# 39-996_-_SM_Clock-Timer.net
KiCad netlist of a schematic drawn in Altium Designer
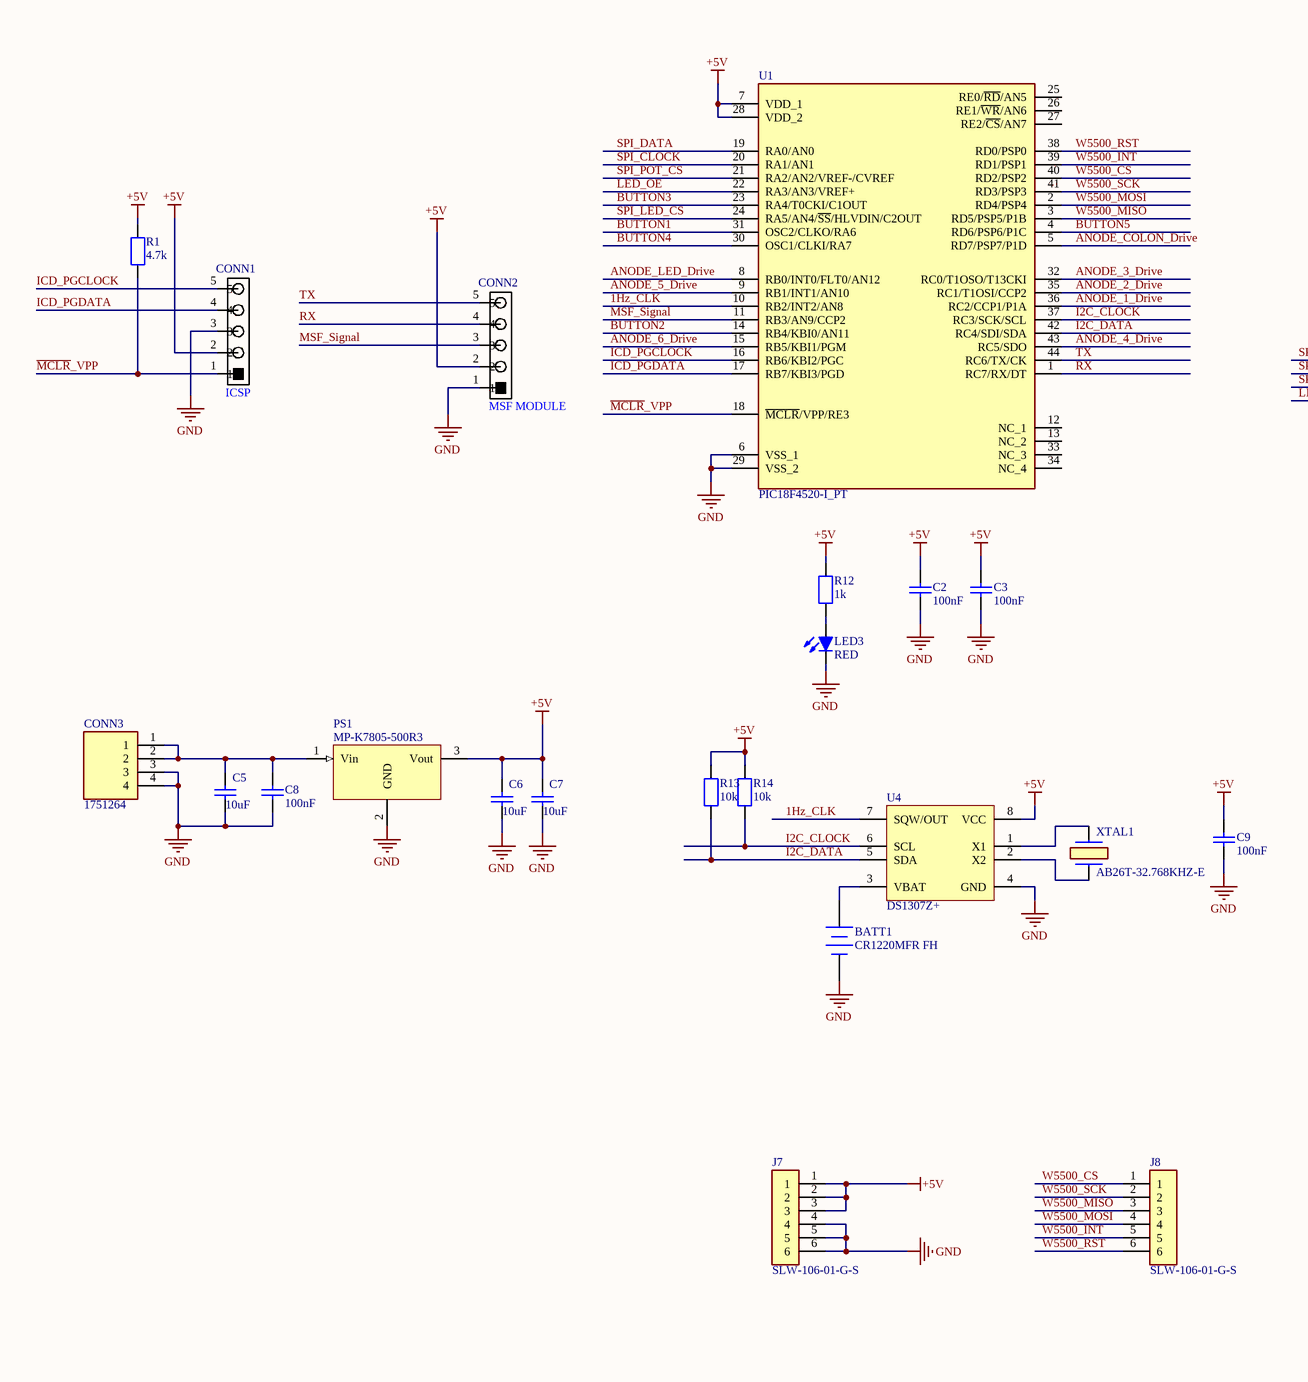
[diagram p0: 39-996 - SM Clock-Timer.SchDoc, left]
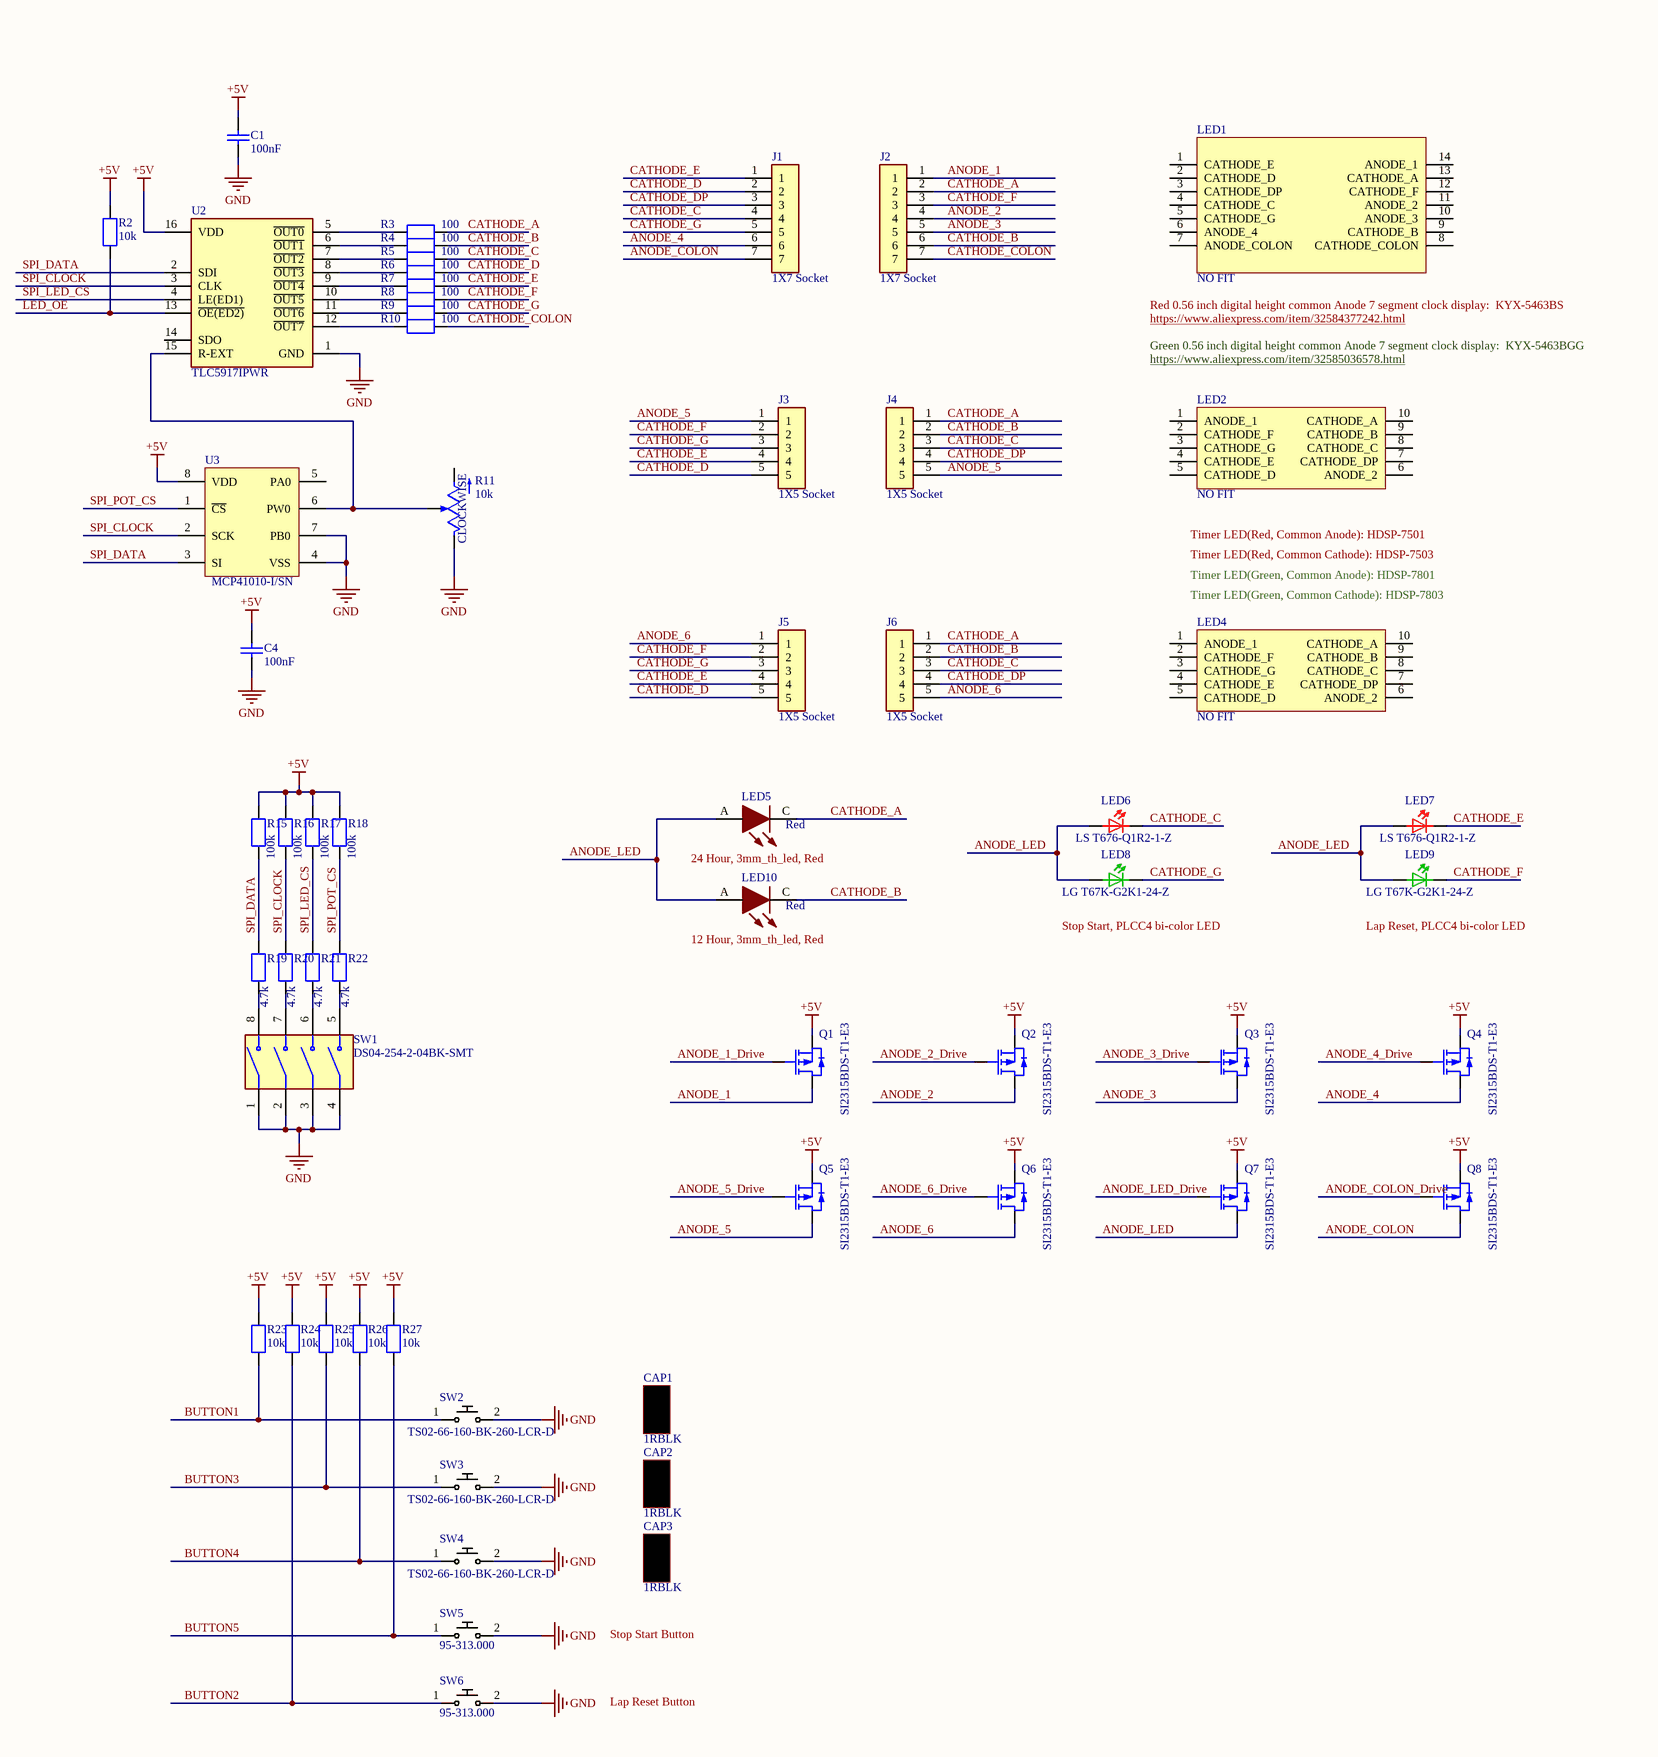
[diagram p1: 39-996 - SM Clock-Timer.SchDoc, right]

(export (version "E")
  (design (tool "Eeschema 10.0.6"))
  (components
    (comp (ref "BATT1")
      (value "CR1220MFR FH")
      (footprint "CR1220MFRFH")
      (description "Coin Cell Battery 3V2-PINHORZ40mAh")
      (fields (field (name "MANUFACTURER") "Renata"))
      (libsource (lib "SM Desk Clock-Timer") (part "CR1220MFR FH"))
    )
    (comp (ref "C1")
      (value "100nF")
      (footprint "C0603")
      (description "100nF ± 10% 50V")
      (fields
        (field (name "MANUFACTURER") "Yageo")
        (field (name "MANUFACTURER PART NUMBER") "CC0603KRX7R9BB104")
      )
      (libsource (lib "Cue Light Output PCB - RJ45") (part "100nF ± 10% 50V"))
    )
    (comp (ref "C2")
      (value "100nF")
      (footprint "C0603")
      (description "100nF ± 10% 50V")
      (fields
        (field (name "MANUFACTURER") "Yageo")
        (field (name "MANUFACTURER PART NUMBER") "CC0603KRX7R9BB104")
      )
      (libsource (lib "Cue Light Output PCB - RJ45") (part "100nF ± 10% 50V"))
    )
    (comp (ref "C3")
      (value "100nF")
      (footprint "C0603")
      (description "100nF ± 10% 50V")
      (fields
        (field (name "MANUFACTURER") "Yageo")
        (field (name "MANUFACTURER PART NUMBER") "CC0603KRX7R9BB104")
      )
      (libsource (lib "Cue Light Output PCB - RJ45") (part "100nF ± 10% 50V"))
    )
    (comp (ref "C4")
      (value "100nF")
      (footprint "C0603")
      (description "100nF ± 10% 50V")
      (fields
        (field (name "MANUFACTURER") "Yageo")
        (field (name "MANUFACTURER PART NUMBER") "CC0603KRX7R9BB104")
      )
      (libsource (lib "Cue Light Output PCB - RJ45") (part "100nF ± 10% 50V"))
    )
    (comp (ref "C5")
      (value "10uF")
      (footprint "C1206")
      (description "10uF ± 10% 50V")
      (fields
        (field (name "MANUFACTURER") "Murata")
        (field (name "MANUFACTURER PART NUMBER") "GRT31CR61H106KE01L")
      )
      (libsource (lib "Cue Light Output PCB - RJ45") (part "10uF ± 10% 50V"))
    )
    (comp (ref "C6")
      (value "10uF")
      (footprint "C1206")
      (description "10uF ± 10% 50V")
      (fields
        (field (name "MANUFACTURER") "Murata")
        (field (name "MANUFACTURER PART NUMBER") "GRT31CR61H106KE01L")
      )
      (libsource (lib "Cue Light Output PCB - RJ45") (part "10uF ± 10% 50V"))
    )
    (comp (ref "C7")
      (value "10uF")
      (footprint "C1206")
      (description "10uF ± 10% 50V")
      (fields
        (field (name "MANUFACTURER") "Murata")
        (field (name "MANUFACTURER PART NUMBER") "GRT31CR61H106KE01L")
      )
      (libsource (lib "Cue Light Output PCB - RJ45") (part "10uF ± 10% 50V"))
    )
    (comp (ref "C8")
      (value "100nF")
      (footprint "C0603")
      (description "100nF ± 10% 50V")
      (fields
        (field (name "MANUFACTURER") "Yageo")
        (field (name "MANUFACTURER PART NUMBER") "CC0603KRX7R9BB104")
      )
      (libsource (lib "Cue Light Output PCB - RJ45") (part "100nF ± 10% 50V"))
    )
    (comp (ref "C9")
      (value "100nF")
      (footprint "C0603")
      (description "100nF ± 10% 50V")
      (fields
        (field (name "MANUFACTURER") "Yageo")
        (field (name "MANUFACTURER PART NUMBER") "CC0603KRX7R9BB104")
      )
      (libsource (lib "Cue Light Output PCB - RJ45") (part "100nF ± 10% 50V"))
    )
    (comp (ref "CAP1")
      (value "1RBLK")
      (footprint "1RBLK")
      (description "Switch Bezels / Switch Caps 9 X 5MM RND CAP BLK")
      (fields (field (name "MANUFACTURER") "E-Switch"))
      (libsource (lib "SM Desk Clock-Timer") (part "1RBLK"))
    )
    (comp (ref "CAP2")
      (value "1RBLK")
      (footprint "1RBLK")
      (description "Switch Bezels / Switch Caps 9 X 5MM RND CAP BLK")
      (fields (field (name "MANUFACTURER") "E-Switch"))
      (libsource (lib "SM Desk Clock-Timer") (part "1RBLK"))
    )
    (comp (ref "CAP3")
      (value "1RBLK")
      (footprint "1RBLK")
      (description "Switch Bezels / Switch Caps 9 X 5MM RND CAP BLK")
      (fields (field (name "MANUFACTURER") "E-Switch"))
      (libsource (lib "SM Desk Clock-Timer") (part "1RBLK"))
    )
    (comp (ref "CONN1")
      (value "NO FIT")
      (footprint "ICSP")
      (description "ICSP Header - 5 Pin, 2.54mm Pitch")
      (libsource (lib "GDS_CONN") (part "ICSP"))
    )
    (comp (ref "CONN2")
      (value "NO FIT")
      (footprint "ICSP")
      (description "ICSP Header - 5 Pin, 2.54mm Pitch")
      (libsource (lib "GDS_CONN") (part "ICSP"))
    )
    (comp (ref "CONN3")
      (value "1751264")
      (footprint "1751264")
      (description "Fixed Terminal Blocks 4P 3.5mm 90DEG")
      (fields (field (name "MANUFACTURER") "Phoenix Contact"))
      (libsource (lib "1751264") (part "1751264"))
    )
    (comp (ref "J1")
      (value "1X7 Socket")
      (footprint "D019970742")
      (description "IC & Component Sockets 7 WAY SIL VERT SKT")
      (fields (field (name "MANUFACTURER") "Harwin") (field (name "MANUFACTURER PART NUMBER") "D01-9970742"))
      (libsource (lib "") (part "D01-9970742_1"))
    )
    (comp (ref "J2")
      (value "1X7 Socket")
      (footprint "D019970742")
      (description "IC & Component Sockets 7 WAY SIL VERT SKT")
      (fields (field (name "MANUFACTURER") "Harwin") (field (name "MANUFACTURER PART NUMBER") "D01-9970742"))
      (libsource (lib "SM Desk Clock-Timer") (part "D01-9970742"))
    )
    (comp (ref "J3")
      (value "1X5 Socket")
      (footprint "D01-9970542")
      (description "IC & Component Sockets 5 WAY SIL VERT SKT")
      (fields (field (name "MANUFACTURER") "Harwin") (field (name "MANUFACTURER PART NUMBER") "D01-9970542"))
      (libsource (lib "SM Desk Clock-Timer") (part "D01-9970542"))
    )
    (comp (ref "J4")
      (value "1X5 Socket")
      (footprint "D01-9970542")
      (description "IC & Component Sockets 5 WAY SIL VERT SKT")
      (fields (field (name "MANUFACTURER") "Harwin") (field (name "MANUFACTURER PART NUMBER") "D01-9970542"))
      (libsource (lib "") (part "D01-9970542_1"))
    )
    (comp (ref "J5")
      (value "1X5 Socket")
      (footprint "D01-9970542")
      (description "IC & Component Sockets 5 WAY SIL VERT SKT")
      (fields (field (name "MANUFACTURER") "Harwin") (field (name "MANUFACTURER PART NUMBER") "D01-9970542"))
      (libsource (lib "SM Desk Clock-Timer") (part "D01-9970542"))
    )
    (comp (ref "J6")
      (value "1X5 Socket")
      (footprint "D01-9970542")
      (description "IC & Component Sockets 5 WAY SIL VERT SKT")
      (fields (field (name "MANUFACTURER") "Harwin") (field (name "MANUFACTURER PART NUMBER") "D01-9970542"))
      (libsource (lib "") (part "D01-9970542_1"))
    )
    (comp (ref "J7")
      (value "SLW-106-01-G-S")
      (footprint "SLW-106-01-G-S")
      (description "Headers & Wire Housings .100\" Tiger Buy Low Profile Socket Strip")
      (fields (field (name "MANUFACTURER") "Samtec"))
      (libsource (lib "SM Desk Clock-Timer") (part "SLW-106-01-G-S"))
    )
    (comp (ref "J8")
      (value "SLW-106-01-G-S")
      (footprint "SLW-106-01-G-S")
      (description "Headers & Wire Housings .100\" Tiger Buy Low Profile Socket Strip")
      (fields (field (name "MANUFACTURER") "Samtec"))
      (libsource (lib "") (part "SLW-106-01-G-S_1"))
    )
    (comp (ref "LED1")
      (value "NO FIT")
      (footprint "Common Cathode 7 Segment Clock Display")
      (description "0.56 inch digit height common Anode 7 segment clock display")
      (libsource (lib "SM Desk Clock-Timer") (part "Common Anode 7 Segment Clock Display"))
    )
    (comp (ref "LED2")
      (value "NO FIT")
      (footprint "HDSP7501")
      (description "7 SEG NUMERIC DISPLAY, HIGH EFFICIENCY RED, 7.6 mm")
      (fields
        (field (name "MANUFACTURER") "Avago Technologies")
        (field (name "MANUFACTURER PART NUMBER") "HDSP-7501")
      )
      (libsource (lib "SM Desk Clock-Timer") (part "HDSP-7501"))
    )
    (comp (ref "LED3")
      (value "RED")
      (footprint "LED_PLCC2")
      (description "Standard LEDs - SMD Super Red, 645nm 180mcd, 20mA")
      (fields
        (field (name "MANUFACTURER") "ams OSRAM")
        (field (name "MANUFACTURER PART NUMBER") "LS T676-Q1R2-1-Z")
      )
      (libsource (lib "Cue Light Output PCB - RJ45") (part "LS T676-Q1R2-1-Z"))
    )
    (comp (ref "LED4")
      (value "NO FIT")
      (footprint "HDSP7501")
      (description "7 SEG NUMERIC DISPLAY, HIGH EFFICIENCY RED, 7.6 mm")
      (fields
        (field (name "MANUFACTURER") "Avago Technologies")
        (field (name "MANUFACTURER PART NUMBER") "HDSP-7501")
      )
      (libsource (lib "SM Desk Clock-Timer") (part "HDSP-7501"))
    )
    (comp (ref "LED5")
      (value "Red")
      (footprint "LED_3mm")
      (description "Standard LEDs - Through Hole RED DIFFUSED")
      (fields (field (name "MANUFACTURER") "Kingbright") (field (name "MANUFACTURER PART NUMBER") "WP132XID"))
      (libsource (lib "SM Desk Clock-Timer") (part "WP132XID"))
    )
    (comp (ref "LED6")
      (value "LS T676-Q1R2-1-Z")
      (footprint "PLCC-2")
      (description "Standard LEDs - SMD Super Red, 645nm 180mcd, 20mA")
      (fields (field (name "MANUFACTURER") "ams OSRAM"))
      (libsource (lib "47-538 - Desk Power CTRL Button") (part "LS T676-Q1R2-1-Z"))
    )
    (comp (ref "LED7")
      (value "LS T676-Q1R2-1-Z")
      (footprint "PLCC-2")
      (description "Standard LEDs - SMD Super Red, 645nm 180mcd, 20mA")
      (fields (field (name "MANUFACTURER") "ams OSRAM"))
      (libsource (lib "47-538 - Desk Power CTRL Button") (part "LS T676-Q1R2-1-Z"))
    )
    (comp (ref "LED8")
      (value "LG T67K-G2K1-24-Z")
      (footprint "PLCC-2")
      (description "Standard LEDs - SMD Green 570nm, 20mA")
      (fields (field (name "MANUFACTURER") "ams OSRAM"))
      (libsource (lib "47-538 - Desk Power CTRL Button") (part "LG T67K-G2K1-24-Z"))
    )
    (comp (ref "LED9")
      (value "LG T67K-G2K1-24-Z")
      (footprint "PLCC-2")
      (description "Standard LEDs - SMD Green 570nm, 20mA")
      (fields (field (name "MANUFACTURER") "ams OSRAM"))
      (libsource (lib "47-538 - Desk Power CTRL Button") (part "LG T67K-G2K1-24-Z"))
    )
    (comp (ref "LED10")
      (value "Red")
      (footprint "LED_3mm")
      (description "Standard LEDs - Through Hole RED DIFFUSED")
      (fields (field (name "MANUFACTURER") "Kingbright") (field (name "MANUFACTURER PART NUMBER") "WP132XID"))
      (libsource (lib "SM Desk Clock-Timer") (part "WP132XID"))
    )
    (comp (ref "PS1")
      (value "MP-K7805-500R3")
      (footprint "CONV_K7805-500R3")
      (fields (field (name "MANUFACTURER") "MULTICOMP PRO"))
      (libsource (lib "SM Desk Clock-Timer") (part "MP-K7805-500R3"))
    )
    (comp (ref "Q1")
      (value "SI2315BDS-T1-E3")
      (footprint "SOT23-3")
      (description "MOSFET 1.8V 3.2A 1.25W")
      (fields (field (name "MANUFACTURER") "Vishay Semiconductors"))
      (libsource (lib "SM Desk Clock-Timer") (part "SI2315BDS-T1-E3"))
    )
    (comp (ref "Q2")
      (value "SI2315BDS-T1-E3")
      (footprint "SOT23-3")
      (description "MOSFET 1.8V 3.2A 1.25W")
      (fields (field (name "MANUFACTURER") "Vishay Semiconductors"))
      (libsource (lib "SM Desk Clock-Timer") (part "SI2315BDS-T1-E3"))
    )
    (comp (ref "Q3")
      (value "SI2315BDS-T1-E3")
      (footprint "SOT23-3")
      (description "MOSFET 1.8V 3.2A 1.25W")
      (fields (field (name "MANUFACTURER") "Vishay Semiconductors"))
      (libsource (lib "SM Desk Clock-Timer") (part "SI2315BDS-T1-E3"))
    )
    (comp (ref "Q4")
      (value "SI2315BDS-T1-E3")
      (footprint "SOT23-3")
      (description "MOSFET 1.8V 3.2A 1.25W")
      (fields (field (name "MANUFACTURER") "Vishay Semiconductors"))
      (libsource (lib "SM Desk Clock-Timer") (part "SI2315BDS-T1-E3"))
    )
    (comp (ref "Q5")
      (value "SI2315BDS-T1-E3")
      (footprint "SOT23-3")
      (description "MOSFET 1.8V 3.2A 1.25W")
      (fields (field (name "MANUFACTURER") "Vishay Semiconductors"))
      (libsource (lib "SM Desk Clock-Timer") (part "SI2315BDS-T1-E3"))
    )
    (comp (ref "Q6")
      (value "SI2315BDS-T1-E3")
      (footprint "SOT23-3")
      (description "MOSFET 1.8V 3.2A 1.25W")
      (fields (field (name "MANUFACTURER") "Vishay Semiconductors"))
      (libsource (lib "SM Desk Clock-Timer") (part "SI2315BDS-T1-E3"))
    )
    (comp (ref "Q7")
      (value "SI2315BDS-T1-E3")
      (footprint "SOT23-3")
      (description "MOSFET 1.8V 3.2A 1.25W")
      (fields (field (name "MANUFACTURER") "Vishay Semiconductors"))
      (libsource (lib "SM Desk Clock-Timer") (part "SI2315BDS-T1-E3"))
    )
    (comp (ref "Q8")
      (value "SI2315BDS-T1-E3")
      (footprint "SOT23-3")
      (description "MOSFET 1.8V 3.2A 1.25W")
      (fields (field (name "MANUFACTURER") "Vishay Semiconductors"))
      (libsource (lib "SM Desk Clock-Timer") (part "SI2315BDS-T1-E3"))
    )
    (comp (ref "R1")
      (value "4.7k")
      (footprint "R0603")
      (description "4.7 kOhms ±1% 0.1W")
      (fields
        (field (name "MANUFACTURER") "Yageo")
        (field (name "MANUFACTURER PART NUMBER") "RC0603FR-074K7L")
      )
      (libsource (lib "32-503 - DriveHUB - 1Ch 10A Variable CV") (part "4.7 kOhms ±1% 0.1W"))
    )
    (comp (ref "R2")
      (value "10k")
      (footprint "R0603")
      (description "10 kOhms ±1% 0.1W")
      (fields
        (field (name "MANUFACTURER") "Yageo")
        (field (name "MANUFACTURER PART NUMBER") "RC0603FR-0710KL")
      )
      (libsource (lib "SM Desk Clock-Timer") (part "10 kOhms ±1% 0.1W"))
    )
    (comp (ref "R3")
      (value "100")
      (footprint "R0603")
      (description "100 Ohms ±1% 0.1W")
      (fields
        (field (name "MANUFACTURER") "Yageo")
        (field (name "MANUFACTURER PART NUMBER") "RC0603FR-07100RL")
      )
      (libsource (lib "SM Desk Clock-Timer") (part "100 Ohms ±1% 0.1W"))
    )
    (comp (ref "R4")
      (value "100")
      (footprint "R0603")
      (description "100 Ohms ±1% 0.1W")
      (fields
        (field (name "MANUFACTURER") "Yageo")
        (field (name "MANUFACTURER PART NUMBER") "RC0603FR-07100RL")
      )
      (libsource (lib "SM Desk Clock-Timer") (part "100 Ohms ±1% 0.1W"))
    )
    (comp (ref "R5")
      (value "100")
      (footprint "R0603")
      (description "100 Ohms ±1% 0.1W")
      (fields
        (field (name "MANUFACTURER") "Yageo")
        (field (name "MANUFACTURER PART NUMBER") "RC0603FR-07100RL")
      )
      (libsource (lib "SM Desk Clock-Timer") (part "100 Ohms ±1% 0.1W"))
    )
    (comp (ref "R6")
      (value "100")
      (footprint "R0603")
      (description "100 Ohms ±1% 0.1W")
      (fields
        (field (name "MANUFACTURER") "Yageo")
        (field (name "MANUFACTURER PART NUMBER") "RC0603FR-07100RL")
      )
      (libsource (lib "SM Desk Clock-Timer") (part "100 Ohms ±1% 0.1W"))
    )
    (comp (ref "R7")
      (value "100")
      (footprint "R0603")
      (description "100 Ohms ±1% 0.1W")
      (fields
        (field (name "MANUFACTURER") "Yageo")
        (field (name "MANUFACTURER PART NUMBER") "RC0603FR-07100RL")
      )
      (libsource (lib "SM Desk Clock-Timer") (part "100 Ohms ±1% 0.1W"))
    )
    (comp (ref "R8")
      (value "100")
      (footprint "R0603")
      (description "100 Ohms ±1% 0.1W")
      (fields
        (field (name "MANUFACTURER") "Yageo")
        (field (name "MANUFACTURER PART NUMBER") "RC0603FR-07100RL")
      )
      (libsource (lib "SM Desk Clock-Timer") (part "100 Ohms ±1% 0.1W"))
    )
    (comp (ref "R9")
      (value "100")
      (footprint "R0603")
      (description "100 Ohms ±1% 0.1W")
      (fields
        (field (name "MANUFACTURER") "Yageo")
        (field (name "MANUFACTURER PART NUMBER") "RC0603FR-07100RL")
      )
      (libsource (lib "SM Desk Clock-Timer") (part "100 Ohms ±1% 0.1W"))
    )
    (comp (ref "R10")
      (value "100")
      (footprint "R0603")
      (description "100 Ohms ±1% 0.1W")
      (fields
        (field (name "MANUFACTURER") "Yageo")
        (field (name "MANUFACTURER PART NUMBER") "RC0603FR-07100RL")
      )
      (libsource (lib "SM Desk Clock-Timer") (part "100 Ohms ±1% 0.1W"))
    )
    (comp (ref "R11")
      (value "10k")
      (footprint "TRIM_3386F-1-103LF")
      (description "Trimmer Resistors - Through Hole 3/8\" 10Kohms 10% 0.5Watts Square")
      (fields
        (field (name "MANUFACTURER") "Bourns")
        (field (name "MANUFACTURER PART NUMBER") "3386F-1-103LF")
      )
      (libsource (lib "SM Desk Clock-Timer") (part "3386F-1-103LF"))
    )
    (comp (ref "R12")
      (value "1k")
      (footprint "R0603")
      (description "1 kOhms ±1% 0.1W")
      (fields
        (field (name "MANUFACTURER") "Yageo")
        (field (name "MANUFACTURER PART NUMBER") "RC0603FR-071KL")
      )
      (libsource (lib "SM Desk Clock-Timer") (part "1 kOhms ±1% 0.1W"))
    )
    (comp (ref "R13")
      (value "10k")
      (footprint "R0603")
      (description "10 kOhms ±1% 0.1W")
      (fields
        (field (name "MANUFACTURER") "Yageo")
        (field (name "MANUFACTURER PART NUMBER") "RC0603FR-0710KL")
      )
      (libsource (lib "SM Desk Clock-Timer") (part "10 kOhms ±1% 0.1W"))
    )
    (comp (ref "R14")
      (value "10k")
      (footprint "R0603")
      (description "10 kOhms ±1% 0.1W")
      (fields
        (field (name "MANUFACTURER") "Yageo")
        (field (name "MANUFACTURER PART NUMBER") "RC0603FR-0710KL")
      )
      (libsource (lib "SM Desk Clock-Timer") (part "10 kOhms ±1% 0.1W"))
    )
    (comp (ref "R15")
      (value "100k")
      (footprint "R0603")
      (description "100 kOhms ±1% 0.1W")
      (fields
        (field (name "MANUFACTURER") "Yageo")
        (field (name "MANUFACTURER PART NUMBER") "RC0603FR-07100KL")
      )
      (libsource (lib "SM Desk Clock-Timer") (part "100 kOhms ±1% 0.1W"))
    )
    (comp (ref "R16")
      (value "100k")
      (footprint "R0603")
      (description "100 kOhms ±1% 0.1W")
      (fields
        (field (name "MANUFACTURER") "Yageo")
        (field (name "MANUFACTURER PART NUMBER") "RC0603FR-07100KL")
      )
      (libsource (lib "SM Desk Clock-Timer") (part "100 kOhms ±1% 0.1W"))
    )
    (comp (ref "R17")
      (value "100k")
      (footprint "R0603")
      (description "100 kOhms ±1% 0.1W")
      (fields
        (field (name "MANUFACTURER") "Yageo")
        (field (name "MANUFACTURER PART NUMBER") "RC0603FR-07100KL")
      )
      (libsource (lib "SM Desk Clock-Timer") (part "100 kOhms ±1% 0.1W"))
    )
    (comp (ref "R18")
      (value "100k")
      (footprint "R0603")
      (description "100 kOhms ±1% 0.1W")
      (fields
        (field (name "MANUFACTURER") "Yageo")
        (field (name "MANUFACTURER PART NUMBER") "RC0603FR-07100KL")
      )
      (libsource (lib "SM Desk Clock-Timer") (part "100 kOhms ±1% 0.1W"))
    )
    (comp (ref "R19")
      (value "4.7k")
      (footprint "R0603")
      (description "4.7 kOhms ±1% 0.1W")
      (fields
        (field (name "MANUFACTURER") "Yageo")
        (field (name "MANUFACTURER PART NUMBER") "RC0603FR-074K7L")
      )
      (libsource (lib "32-503 - DriveHUB - 1Ch 10A Variable CV") (part "4.7 kOhms ±1% 0.1W"))
    )
    (comp (ref "R20")
      (value "4.7k")
      (footprint "R0603")
      (description "4.7 kOhms ±1% 0.1W")
      (fields
        (field (name "MANUFACTURER") "Yageo")
        (field (name "MANUFACTURER PART NUMBER") "RC0603FR-074K7L")
      )
      (libsource (lib "32-503 - DriveHUB - 1Ch 10A Variable CV") (part "4.7 kOhms ±1% 0.1W"))
    )
    (comp (ref "R21")
      (value "4.7k")
      (footprint "R0603")
      (description "4.7 kOhms ±1% 0.1W")
      (fields
        (field (name "MANUFACTURER") "Yageo")
        (field (name "MANUFACTURER PART NUMBER") "RC0603FR-074K7L")
      )
      (libsource (lib "32-503 - DriveHUB - 1Ch 10A Variable CV") (part "4.7 kOhms ±1% 0.1W"))
    )
    (comp (ref "R22")
      (value "4.7k")
      (footprint "R0603")
      (description "4.7 kOhms ±1% 0.1W")
      (fields
        (field (name "MANUFACTURER") "Yageo")
        (field (name "MANUFACTURER PART NUMBER") "RC0603FR-074K7L")
      )
      (libsource (lib "32-503 - DriveHUB - 1Ch 10A Variable CV") (part "4.7 kOhms ±1% 0.1W"))
    )
    (comp (ref "R23")
      (value "10k")
      (footprint "R0603")
      (description "10 kOhms ±1% 0.1W")
      (fields
        (field (name "MANUFACTURER") "Yageo")
        (field (name "MANUFACTURER PART NUMBER") "RC0603FR-0710KL")
      )
      (libsource (lib "SM Desk Clock-Timer") (part "10 kOhms ±1% 0.1W"))
    )
    (comp (ref "R24")
      (value "10k")
      (footprint "R0603")
      (description "10 kOhms ±1% 0.1W")
      (fields
        (field (name "MANUFACTURER") "Yageo")
        (field (name "MANUFACTURER PART NUMBER") "RC0603FR-0710KL")
      )
      (libsource (lib "SM Desk Clock-Timer") (part "10 kOhms ±1% 0.1W"))
    )
    (comp (ref "R25")
      (value "10k")
      (footprint "R0603")
      (description "10 kOhms ±1% 0.1W")
      (fields
        (field (name "MANUFACTURER") "Yageo")
        (field (name "MANUFACTURER PART NUMBER") "RC0603FR-0710KL")
      )
      (libsource (lib "SM Desk Clock-Timer") (part "10 kOhms ±1% 0.1W"))
    )
    (comp (ref "R26")
      (value "10k")
      (footprint "R0603")
      (description "10 kOhms ±1% 0.1W")
      (fields
        (field (name "MANUFACTURER") "Yageo")
        (field (name "MANUFACTURER PART NUMBER") "RC0603FR-0710KL")
      )
      (libsource (lib "SM Desk Clock-Timer") (part "10 kOhms ±1% 0.1W"))
    )
    (comp (ref "R27")
      (value "10k")
      (footprint "R0603")
      (description "10 kOhms ±1% 0.1W")
      (fields
        (field (name "MANUFACTURER") "Yageo")
        (field (name "MANUFACTURER PART NUMBER") "RC0603FR-0710KL")
      )
      (libsource (lib "SM Desk Clock-Timer") (part "10 kOhms ±1% 0.1W"))
    )
    (comp (ref "SW1")
      (value "DS04-254-2-04BK-SMT")
      (footprint "SW_DS04-254-2-04BK-SMT")
      (description "DIP Switches/SIP Switches DIP Switch, SPST, 2.54 pitch, flat actuator, SMT, 4 position, Black")
      (fields (field (name "MANUFACTURER") "CUI Devices"))
      (libsource (lib "SM Desk Clock-Timer") (part "DS04-254-2-04BK-SMT"))
    )
    (comp (ref "SW2")
      (value "TS02-66-160-BK-260-LCR-D")
      (footprint "SW_TS02-66-160-BK-260-LCR-D")
      (description "Tactile Switches 6 x 6 mm, 16 mm Act Height, 260 gf, Black, Long Crimped, Through Hole, SPST,")
      (fields (field (name "MANUFACTURER") "CUI Devices"))
      (libsource (lib "SM Desk Clock-Timer") (part "TS02-66-160-BK-260-LCR-D"))
    )
    (comp (ref "SW3")
      (value "TS02-66-160-BK-260-LCR-D")
      (footprint "SW_TS02-66-160-BK-260-LCR-D")
      (description "Tactile Switches 6 x 6 mm, 16 mm Act Height, 260 gf, Black, Long Crimped, Through Hole, SPST,")
      (fields (field (name "MANUFACTURER") "CUI Devices"))
      (libsource (lib "SM Desk Clock-Timer") (part "TS02-66-160-BK-260-LCR-D"))
    )
    (comp (ref "SW4")
      (value "TS02-66-160-BK-260-LCR-D")
      (footprint "SW_TS02-66-160-BK-260-LCR-D")
      (description "Tactile Switches 6 x 6 mm, 16 mm Act Height, 260 gf, Black, Long Crimped, Through Hole, SPST,")
      (fields (field (name "MANUFACTURER") "CUI Devices"))
      (libsource (lib "SM Desk Clock-Timer") (part "TS02-66-160-BK-260-LCR-D"))
    )
    (comp (ref "SW5")
      (value "95-313.000")
      (footprint "PUSHBUTTON_95-313.000")
      (description "Switching element square, 12.7 x 12.7 mm")
      (fields (field (name "MANUFACTURER") "eao"))
      (libsource (lib "47-538 - Desk Power CTRL Button") (part "95-313.000"))
    )
    (comp (ref "SW6")
      (value "95-313.000")
      (footprint "PUSHBUTTON_95-313.000")
      (description "Switching element square, 12.7 x 12.7 mm")
      (fields (field (name "MANUFACTURER") "eao"))
      (libsource (lib "47-538 - Desk Power CTRL Button") (part "95-313.000"))
    )
    (comp (ref "U1")
      (value "PIC18F4520-I_PT")
      (footprint "TQFP-44")
      (description "MCU 32 KB Flash,1536 RAM, 36 I/O")
      (fields
        (field (name "MANUFACTURER") "Microchip")
        (field (name "MANUFACTURER PART NUMBER") "PIC18F4520-I/PT")
      )
      (libsource (lib "SM Desk Clock-Timer") (part "PIC18F4520-I_PT"))
    )
    (comp (ref "U2")
      (value "TLC5917IPWR")
      (footprint "SOIC-16")
      (description "LED Lighting Drivers 8B Constant-Current LED Sink")
      (fields (field (name "MANUFACTURER") "Texas Instruments"))
      (libsource (lib "SM Desk Clock-Timer") (part "TLC5917IPWR"))
    )
    (comp (ref "U3")
      (value "MCP41010-I/SN")
      (footprint "SOIC-8")
      (description "Digital Potentiometer 10K 256pos SPI SO8")
      (fields (field (name "MANUFACTURER") "Microchip"))
      (libsource (lib "SM Desk Clock-Timer") (part "MCP41010-I/SN"))
    )
    (comp (ref "U4")
      (value "DS1307Z+")
      (footprint "SOIC-8")
      (description "DS1307Z+, Real Time Clock, Alarm, Calendar, Clock, 56B RAM, I2C, 5V, 8-Pin SOIC")
      (fields (field (name "MANUFACTURER") "Analog Devices"))
      (libsource (lib "SM Desk Clock-Timer") (part "DS1307Z+"))
    )
    (comp (ref "XTAL1")
      (value "AB26T-32.768KHZ-E")
      (footprint "AB26T32768KHZE")
      (description "OSC XO 1.33GHZ 2.5V LVPECL")
      (fields (field (name "MANUFACTURER") "ABRACON"))
      (libsource (lib "SM Desk Clock-Timer") (part "AB26T-32.768KHZ-E"))
    )
  )
  (nets
    (net (code "1") (name "+5V") (class "Default")
      (node (ref "C1") (pin "2") (pinfunction "2_2") (pintype "passive"))
      (node (ref "C2") (pin "2") (pinfunction "2_2") (pintype "passive"))
      (node (ref "C3") (pin "2") (pinfunction "2_2") (pintype "passive"))
      (node (ref "C4") (pin "2") (pinfunction "2_2") (pintype "passive"))
      (node (ref "C6") (pin "2") (pinfunction "2_2") (pintype "passive"))
      (node (ref "C7") (pin "2") (pinfunction "2_2") (pintype "passive"))
      (node (ref "C9") (pin "2") (pinfunction "2_2") (pintype "passive"))
      (node (ref "CONN1") (pin "2") (pinfunction "2_2") (pintype "passive"))
      (node (ref "CONN2") (pin "2") (pinfunction "2_2") (pintype "passive"))
      (node (ref "J7") (pin "1") (pinfunction "1_1") (pintype "passive"))
      (node (ref "J7") (pin "2") (pinfunction "2_2") (pintype "passive"))
      (node (ref "J7") (pin "3") (pinfunction "3_3") (pintype "passive"))
      (node (ref "PS1") (pin "3") (pinfunction "Vout_3") (pintype "passive"))
      (node (ref "Q1") (pin "2") (pinfunction "S_2") (pintype "passive"))
      (node (ref "Q2") (pin "2") (pinfunction "S_2") (pintype "passive"))
      (node (ref "Q3") (pin "2") (pinfunction "S_2") (pintype "passive"))
      (node (ref "Q4") (pin "2") (pinfunction "S_2") (pintype "passive"))
      (node (ref "Q5") (pin "2") (pinfunction "S_2") (pintype "passive"))
      (node (ref "Q6") (pin "2") (pinfunction "S_2") (pintype "passive"))
      (node (ref "Q7") (pin "2") (pinfunction "S_2") (pintype "passive"))
      (node (ref "Q8") (pin "2") (pinfunction "S_2") (pintype "passive"))
      (node (ref "R1") (pin "2") (pinfunction "2_2") (pintype "passive"))
      (node (ref "R12") (pin "2") (pinfunction "2_2") (pintype "passive"))
      (node (ref "R13") (pin "2") (pinfunction "2_2") (pintype "passive"))
      (node (ref "R14") (pin "2") (pinfunction "2_2") (pintype "passive"))
      (node (ref "R15") (pin "2") (pinfunction "2_2") (pintype "passive"))
      (node (ref "R16") (pin "2") (pinfunction "2_2") (pintype "passive"))
      (node (ref "R17") (pin "2") (pinfunction "2_2") (pintype "passive"))
      (node (ref "R18") (pin "2") (pinfunction "2_2") (pintype "passive"))
      (node (ref "R2") (pin "2") (pinfunction "2_2") (pintype "passive"))
      (node (ref "R23") (pin "2") (pinfunction "2_2") (pintype "passive"))
      (node (ref "R24") (pin "2") (pinfunction "2_2") (pintype "passive"))
      (node (ref "R25") (pin "2") (pinfunction "2_2") (pintype "passive"))
      (node (ref "R26") (pin "2") (pinfunction "2_2") (pintype "passive"))
      (node (ref "R27") (pin "2") (pinfunction "2_2") (pintype "passive"))
      (node (ref "U1") (pin "28") (pinfunction "VDD_2_28") (pintype "passive"))
      (node (ref "U1") (pin "7") (pinfunction "VDD_1_7") (pintype "passive"))
      (node (ref "U2") (pin "16") (pinfunction "VDD_16") (pintype "passive"))
      (node (ref "U3") (pin "8") (pinfunction "VDD_8") (pintype "passive"))
      (node (ref "U4") (pin "8") (pinfunction "VCC_8") (pintype "passive"))
    )
    (net (code "2") (name "/1Hz_CLK") (class "Default")
      (node (ref "U1") (pin "10") (pinfunction "RB2/INT2/AN8_10") (pintype "passive"))
      (node (ref "U4") (pin "7") (pinfunction "SQW/OUT_7") (pintype "passive"))
    )
    (net (code "3") (name "/ANODE_1") (class "Default")
      (node (ref "J2") (pin "1") (pinfunction "1_1") (pintype "passive"))
      (node (ref "Q1") (pin "3") (pinfunction "D_3") (pintype "passive"))
    )
    (net (code "4") (name "/ANODE_1_Drive") (class "Default")
      (node (ref "Q1") (pin "1") (pinfunction "G_1") (pintype "passive"))
      (node (ref "U1") (pin "36") (pinfunction "RC2/CCP1/P1A_36") (pintype "passive"))
    )
    (net (code "5") (name "/ANODE_2") (class "Default")
      (node (ref "J2") (pin "4") (pinfunction "4_4") (pintype "passive"))
      (node (ref "Q2") (pin "3") (pinfunction "D_3") (pintype "passive"))
    )
    (net (code "6") (name "/ANODE_2_Drive") (class "Default")
      (node (ref "Q2") (pin "1") (pinfunction "G_1") (pintype "passive"))
      (node (ref "U1") (pin "35") (pinfunction "RC1/T1OSI/CCP2_35") (pintype "passive"))
    )
    (net (code "7") (name "/ANODE_3") (class "Default")
      (node (ref "J2") (pin "5") (pinfunction "5_5") (pintype "passive"))
      (node (ref "Q3") (pin "3") (pinfunction "D_3") (pintype "passive"))
    )
    (net (code "8") (name "/ANODE_3_Drive") (class "Default")
      (node (ref "Q3") (pin "1") (pinfunction "G_1") (pintype "passive"))
      (node (ref "U1") (pin "32") (pinfunction "RC0/T1OSO/T13CKI_32") (pintype "passive"))
    )
    (net (code "9") (name "/ANODE_4") (class "Default")
      (node (ref "J1") (pin "6") (pinfunction "6_6") (pintype "passive"))
      (node (ref "Q4") (pin "3") (pinfunction "D_3") (pintype "passive"))
    )
    (net (code "10") (name "/ANODE_4_Drive") (class "Default")
      (node (ref "Q4") (pin "1") (pinfunction "G_1") (pintype "passive"))
      (node (ref "U1") (pin "43") (pinfunction "RC5/SDO_43") (pintype "passive"))
    )
    (net (code "11") (name "/ANODE_5") (class "Default")
      (node (ref "J3") (pin "1") (pinfunction "1_1") (pintype "passive"))
      (node (ref "J4") (pin "5") (pinfunction "5_5") (pintype "passive"))
      (node (ref "Q5") (pin "3") (pinfunction "D_3") (pintype "passive"))
    )
    (net (code "12") (name "/ANODE_5_Drive") (class "Default")
      (node (ref "Q5") (pin "1") (pinfunction "G_1") (pintype "passive"))
      (node (ref "U1") (pin "9") (pinfunction "RB1/INT1/AN10_9") (pintype "passive"))
    )
    (net (code "13") (name "/ANODE_6") (class "Default")
      (node (ref "J5") (pin "1") (pinfunction "1_1") (pintype "passive"))
      (node (ref "J6") (pin "5") (pinfunction "5_5") (pintype "passive"))
      (node (ref "Q6") (pin "3") (pinfunction "D_3") (pintype "passive"))
    )
    (net (code "14") (name "/ANODE_6_Drive") (class "Default")
      (node (ref "Q6") (pin "1") (pinfunction "G_1") (pintype "passive"))
      (node (ref "U1") (pin "15") (pinfunction "RB5/KBI1/PGM_15") (pintype "passive"))
    )
    (net (code "15") (name "/ANODE_COLON") (class "Default")
      (node (ref "J1") (pin "7") (pinfunction "7_7") (pintype "passive"))
      (node (ref "Q8") (pin "3") (pinfunction "D_3") (pintype "passive"))
    )
    (net (code "16") (name "/ANODE_COLON_Drive") (class "Default")
      (node (ref "Q8") (pin "1") (pinfunction "G_1") (pintype "passive"))
      (node (ref "U1") (pin "5") (pinfunction "RD7/PSP7/P1D_5") (pintype "passive"))
    )
    (net (code "17") (name "/ANODE_LED") (class "Default")
      (node (ref "LED10") (pin "A") (pinfunction "A_A") (pintype "passive"))
      (node (ref "LED5") (pin "A") (pinfunction "A_A") (pintype "passive"))
      (node (ref "LED6") (pin "A") (pinfunction "A_A") (pintype "passive"))
      (node (ref "LED7") (pin "A") (pinfunction "A_A") (pintype "passive"))
      (node (ref "LED8") (pin "A") (pinfunction "A_A") (pintype "passive"))
      (node (ref "LED9") (pin "A") (pinfunction "A_A") (pintype "passive"))
      (node (ref "Q7") (pin "3") (pinfunction "D_3") (pintype "passive"))
    )
    (net (code "18") (name "/ANODE_LED_Drive") (class "Default")
      (node (ref "Q7") (pin "1") (pinfunction "G_1") (pintype "passive"))
      (node (ref "U1") (pin "8") (pinfunction "RB0/INT0/FLT0/AN12_8") (pintype "passive"))
    )
    (net (code "19") (name "/BUTTON1") (class "Default")
      (node (ref "R23") (pin "1") (pinfunction "1_1") (pintype "passive"))
      (node (ref "SW2") (pin "1") (pinfunction "1_1") (pintype "passive"))
      (node (ref "U1") (pin "31") (pinfunction "OSC2/CLKO/RA6_31") (pintype "passive"))
    )
    (net (code "20") (name "/BUTTON2") (class "Default")
      (node (ref "R24") (pin "1") (pinfunction "1_1") (pintype "passive"))
      (node (ref "SW6") (pin "1") (pinfunction "1_1") (pintype "passive"))
      (node (ref "U1") (pin "14") (pinfunction "RB4/KBI0/AN11_14") (pintype "passive"))
    )
    (net (code "21") (name "/BUTTON3") (class "Default")
      (node (ref "R25") (pin "1") (pinfunction "1_1") (pintype "passive"))
      (node (ref "SW3") (pin "1") (pinfunction "1_1") (pintype "passive"))
      (node (ref "U1") (pin "23") (pinfunction "RA4/T0CKI/C1OUT_23") (pintype "passive"))
    )
    (net (code "22") (name "/BUTTON4") (class "Default")
      (node (ref "R26") (pin "1") (pinfunction "1_1") (pintype "passive"))
      (node (ref "SW4") (pin "1") (pinfunction "1_1") (pintype "passive"))
      (node (ref "U1") (pin "30") (pinfunction "OSC1/CLKI/RA7_30") (pintype "passive"))
    )
    (net (code "23") (name "/BUTTON5") (class "Default")
      (node (ref "R27") (pin "1") (pinfunction "1_1") (pintype "passive"))
      (node (ref "SW5") (pin "1") (pinfunction "1_1") (pintype "passive"))
      (node (ref "U1") (pin "4") (pinfunction "RD6/PSP6/P1C_4") (pintype "passive"))
    )
    (net (code "24") (name "/CATHODE_A") (class "Default")
      (node (ref "J2") (pin "2") (pinfunction "2_2") (pintype "passive"))
      (node (ref "J4") (pin "1") (pinfunction "1_1") (pintype "passive"))
      (node (ref "J6") (pin "1") (pinfunction "1_1") (pintype "passive"))
      (node (ref "LED5") (pin "C") (pinfunction "C_C") (pintype "passive"))
      (node (ref "R3") (pin "2") (pinfunction "2_2") (pintype "passive"))
    )
    (net (code "25") (name "/CATHODE_B") (class "Default")
      (node (ref "J2") (pin "6") (pinfunction "6_6") (pintype "passive"))
      (node (ref "J4") (pin "2") (pinfunction "2_2") (pintype "passive"))
      (node (ref "J6") (pin "2") (pinfunction "2_2") (pintype "passive"))
      (node (ref "LED10") (pin "C") (pinfunction "C_C") (pintype "passive"))
      (node (ref "R4") (pin "2") (pinfunction "2_2") (pintype "passive"))
    )
    (net (code "26") (name "/CATHODE_C") (class "Default")
      (node (ref "J1") (pin "4") (pinfunction "4_4") (pintype "passive"))
      (node (ref "J4") (pin "3") (pinfunction "3_3") (pintype "passive"))
      (node (ref "J6") (pin "3") (pinfunction "3_3") (pintype "passive"))
      (node (ref "LED6") (pin "C") (pinfunction "C_C") (pintype "passive"))
      (node (ref "R5") (pin "2") (pinfunction "2_2") (pintype "passive"))
    )
    (net (code "27") (name "/CATHODE_COLON") (class "Default")
      (node (ref "J2") (pin "7") (pinfunction "7_7") (pintype "passive"))
      (node (ref "R10") (pin "2") (pinfunction "2_2") (pintype "passive"))
    )
    (net (code "28") (name "/CATHODE_D") (class "Default")
      (node (ref "J1") (pin "2") (pinfunction "2_2") (pintype "passive"))
      (node (ref "J3") (pin "5") (pinfunction "5_5") (pintype "passive"))
      (node (ref "J5") (pin "5") (pinfunction "5_5") (pintype "passive"))
      (node (ref "R6") (pin "2") (pinfunction "2_2") (pintype "passive"))
    )
    (net (code "29") (name "/CATHODE_DP") (class "Default")
      (node (ref "J1") (pin "3") (pinfunction "3_3") (pintype "passive"))
      (node (ref "J4") (pin "4") (pinfunction "4_4") (pintype "passive"))
      (node (ref "J6") (pin "4") (pinfunction "4_4") (pintype "passive"))
    )
    (net (code "30") (name "/CATHODE_E") (class "Default")
      (node (ref "J1") (pin "1") (pinfunction "1_1") (pintype "passive"))
      (node (ref "J3") (pin "4") (pinfunction "4_4") (pintype "passive"))
      (node (ref "J5") (pin "4") (pinfunction "4_4") (pintype "passive"))
      (node (ref "LED7") (pin "C") (pinfunction "C_C") (pintype "passive"))
      (node (ref "R7") (pin "2") (pinfunction "2_2") (pintype "passive"))
    )
    (net (code "31") (name "/CATHODE_F") (class "Default")
      (node (ref "J2") (pin "3") (pinfunction "3_3") (pintype "passive"))
      (node (ref "J3") (pin "2") (pinfunction "2_2") (pintype "passive"))
      (node (ref "J5") (pin "2") (pinfunction "2_2") (pintype "passive"))
      (node (ref "LED9") (pin "C") (pinfunction "C_C") (pintype "passive"))
      (node (ref "R8") (pin "2") (pinfunction "2_2") (pintype "passive"))
    )
    (net (code "32") (name "/CATHODE_G") (class "Default")
      (node (ref "J1") (pin "5") (pinfunction "5_5") (pintype "passive"))
      (node (ref "J3") (pin "3") (pinfunction "3_3") (pintype "passive"))
      (node (ref "J5") (pin "3") (pinfunction "3_3") (pintype "passive"))
      (node (ref "LED8") (pin "C") (pinfunction "C_C") (pintype "passive"))
      (node (ref "R9") (pin "2") (pinfunction "2_2") (pintype "passive"))
    )
    (net (code "33") (name "/I2C_CLOCK") (class "Default")
      (node (ref "R14") (pin "1") (pinfunction "1_1") (pintype "passive"))
      (node (ref "U1") (pin "37") (pinfunction "RC3/SCK/SCL_37") (pintype "passive"))
      (node (ref "U4") (pin "6") (pinfunction "SCL_6") (pintype "passive"))
    )
    (net (code "34") (name "/I2C_DATA") (class "Default")
      (node (ref "R13") (pin "1") (pinfunction "1_1") (pintype "passive"))
      (node (ref "U1") (pin "42") (pinfunction "RC4/SDI/SDA_42") (pintype "passive"))
      (node (ref "U4") (pin "5") (pinfunction "SDA_5") (pintype "passive"))
    )
    (net (code "35") (name "/ICD_PGCLOCK") (class "Default")
      (node (ref "CONN1") (pin "5") (pinfunction "5_5") (pintype "passive"))
      (node (ref "U1") (pin "16") (pinfunction "RB6/KBI2/PGC_16") (pintype "passive"))
    )
    (net (code "36") (name "/ICD_PGDATA") (class "Default")
      (node (ref "CONN1") (pin "4") (pinfunction "4_4") (pintype "passive"))
      (node (ref "U1") (pin "17") (pinfunction "RB7/KBI3/PGD_17") (pintype "passive"))
    )
    (net (code "37") (name "/MSF_Signal") (class "Default")
      (node (ref "CONN2") (pin "3") (pinfunction "3_3") (pintype "passive"))
      (node (ref "U1") (pin "11") (pinfunction "RB3/AN9/CCP2_11") (pintype "passive"))
    )
    (net (code "38") (name "/RX") (class "Default")
      (node (ref "CONN2") (pin "4") (pinfunction "4_4") (pintype "passive"))
      (node (ref "U1") (pin "1") (pinfunction "RC7/RX/DT_1") (pintype "passive"))
    )
    (net (code "39") (name "/SPI_CLOCK") (class "Default")
      (node (ref "R16") (pin "1") (pinfunction "1_1") (pintype "passive"))
      (node (ref "R20") (pin "2") (pinfunction "2_2") (pintype "passive"))
      (node (ref "U1") (pin "20") (pinfunction "RA1/AN1_20") (pintype "passive"))
      (node (ref "U2") (pin "3") (pinfunction "CLK_3") (pintype "passive"))
      (node (ref "U3") (pin "2") (pinfunction "SCK_2") (pintype "passive"))
    )
    (net (code "40") (name "/SPI_DATA") (class "Default")
      (node (ref "R15") (pin "1") (pinfunction "1_1") (pintype "passive"))
      (node (ref "R19") (pin "2") (pinfunction "2_2") (pintype "passive"))
      (node (ref "U1") (pin "19") (pinfunction "RA0/AN0_19") (pintype "passive"))
      (node (ref "U2") (pin "2") (pinfunction "SDI_2") (pintype "passive"))
      (node (ref "U3") (pin "3") (pinfunction "SI_3") (pintype "passive"))
    )
    (net (code "41") (name "/SPI_LED_CS") (class "Default")
      (node (ref "R17") (pin "1") (pinfunction "1_1") (pintype "passive"))
      (node (ref "R21") (pin "2") (pinfunction "2_2") (pintype "passive"))
      (node (ref "U1") (pin "24") (pinfunction "RA5/AN4/~{SS}/HLVDIN/C2OUT_24") (pintype "passive"))
      (node (ref "U2") (pin "4") (pinfunction "LE(ED1)_4") (pintype "passive"))
    )
    (net (code "42") (name "/SPI_POT_CS") (class "Default")
      (node (ref "R18") (pin "1") (pinfunction "1_1") (pintype "passive"))
      (node (ref "R22") (pin "2") (pinfunction "2_2") (pintype "passive"))
      (node (ref "U1") (pin "21") (pinfunction "RA2/AN2/VREF-/CVREF_21") (pintype "passive"))
      (node (ref "U3") (pin "1") (pinfunction "~{CS}_1") (pintype "passive"))
    )
    (net (code "43") (name "/TX") (class "Default")
      (node (ref "CONN2") (pin "5") (pinfunction "5_5") (pintype "passive"))
      (node (ref "U1") (pin "44") (pinfunction "RC6/TX/CK_44") (pintype "passive"))
    )
    (net (code "44") (name "/W5500_CS") (class "Default")
      (node (ref "J8") (pin "1") (pinfunction "1_1") (pintype "passive"))
      (node (ref "U1") (pin "40") (pinfunction "RD2/PSP2_40") (pintype "passive"))
    )
    (net (code "45") (name "/W5500_INT") (class "Default")
      (node (ref "J8") (pin "5") (pinfunction "5_5") (pintype "passive"))
      (node (ref "U1") (pin "39") (pinfunction "RD1/PSP1_39") (pintype "passive"))
    )
    (net (code "46") (name "/W5500_MISO") (class "Default")
      (node (ref "J8") (pin "3") (pinfunction "3_3") (pintype "passive"))
      (node (ref "U1") (pin "3") (pinfunction "RD5/PSP5/P1B_3") (pintype "passive"))
    )
    (net (code "47") (name "/W5500_MOSI") (class "Default")
      (node (ref "J8") (pin "4") (pinfunction "4_4") (pintype "passive"))
      (node (ref "U1") (pin "2") (pinfunction "RD4/PSP4_2") (pintype "passive"))
    )
    (net (code "48") (name "/W5500_RST") (class "Default")
      (node (ref "J8") (pin "6") (pinfunction "6_6") (pintype "passive"))
      (node (ref "U1") (pin "38") (pinfunction "RD0/PSP0_38") (pintype "passive"))
    )
    (net (code "49") (name "/W5500_SCK") (class "Default")
      (node (ref "J8") (pin "2") (pinfunction "2_2") (pintype "passive"))
      (node (ref "U1") (pin "41") (pinfunction "RD3/PSP3_41") (pintype "passive"))
    )
    (net (code "50") (name "/~{LED_OE}") (class "Default")
      (node (ref "R2") (pin "1") (pinfunction "1_1") (pintype "passive"))
      (node (ref "U1") (pin "22") (pinfunction "RA3/AN3/VREF+_22") (pintype "passive"))
      (node (ref "U2") (pin "13") (pinfunction "~{OE(ED2)}_13") (pintype "passive"))
    )
    (net (code "51") (name "/~{MCLR}_VPP") (class "Default")
      (node (ref "CONN1") (pin "1") (pinfunction "1_1") (pintype "passive"))
      (node (ref "R1") (pin "1") (pinfunction "1_1") (pintype "passive"))
      (node (ref "U1") (pin "18") (pinfunction "~{MCLR}/VPP/RE3_18") (pintype "passive"))
    )
    (net (code "52") (name "GND") (class "Default")
      (node (ref "BATT1") (pin "-") (pinfunction "-_-") (pintype "passive"))
      (node (ref "C1") (pin "1") (pinfunction "1_1") (pintype "passive"))
      (node (ref "C2") (pin "1") (pinfunction "1_1") (pintype "passive"))
      (node (ref "C3") (pin "1") (pinfunction "1_1") (pintype "passive"))
      (node (ref "C4") (pin "1") (pinfunction "1_1") (pintype "passive"))
      (node (ref "C5") (pin "1") (pinfunction "1_1") (pintype "passive"))
      (node (ref "C6") (pin "1") (pinfunction "1_1") (pintype "passive"))
      (node (ref "C7") (pin "1") (pinfunction "1_1") (pintype "passive"))
      (node (ref "C8") (pin "1") (pinfunction "1_1") (pintype "passive"))
      (node (ref "C9") (pin "1") (pinfunction "1_1") (pintype "passive"))
      (node (ref "CONN1") (pin "3") (pinfunction "3_3") (pintype "passive"))
      (node (ref "CONN2") (pin "1") (pinfunction "1_1") (pintype "passive"))
      (node (ref "CONN3") (pin "3") (pinfunction "3_3") (pintype "passive"))
      (node (ref "CONN3") (pin "4") (pinfunction "4_4") (pintype "passive"))
      (node (ref "J7") (pin "4") (pinfunction "4_4") (pintype "passive"))
      (node (ref "J7") (pin "5") (pinfunction "5_5") (pintype "passive"))
      (node (ref "J7") (pin "6") (pinfunction "6_6") (pintype "passive"))
      (node (ref "LED3") (pin "1") (pinfunction "1_1") (pintype "passive"))
      (node (ref "PS1") (pin "2") (pinfunction "GND_2") (pintype "passive"))
      (node (ref "R11") (pin "1") (pinfunction "CCW_1") (pintype "passive"))
      (node (ref "SW1") (pin "1") (pinfunction "1_1") (pintype "passive"))
      (node (ref "SW1") (pin "2") (pinfunction "2_2") (pintype "passive"))
      (node (ref "SW1") (pin "3") (pinfunction "3_3") (pintype "passive"))
      (node (ref "SW1") (pin "4") (pinfunction "4_4") (pintype "passive"))
      (node (ref "SW2") (pin "2") (pinfunction "2_2") (pintype "passive"))
      (node (ref "SW3") (pin "2") (pinfunction "2_2") (pintype "passive"))
      (node (ref "SW4") (pin "2") (pinfunction "2_2") (pintype "passive"))
      (node (ref "SW5") (pin "2") (pinfunction "2_2") (pintype "passive"))
      (node (ref "SW6") (pin "2") (pinfunction "2_2") (pintype "passive"))
      (node (ref "U1") (pin "29") (pinfunction "VSS_2_29") (pintype "passive"))
      (node (ref "U1") (pin "6") (pinfunction "VSS_1_6") (pintype "passive"))
      (node (ref "U2") (pin "1") (pinfunction "GND_1") (pintype "passive"))
      (node (ref "U3") (pin "4") (pinfunction "VSS_4") (pintype "passive"))
      (node (ref "U3") (pin "7") (pinfunction "PB0_7") (pintype "passive"))
      (node (ref "U4") (pin "4") (pinfunction "GND_4") (pintype "passive"))
    )
    (net (code "53") (name "Net-(LED3-Pad2)") (class "Default")
      (node (ref "LED3") (pin "2") (pinfunction "2_2") (pintype "passive"))
      (node (ref "R12") (pin "1") (pinfunction "1_1") (pintype "passive"))
    )
    (net (code "54") (name "Net-(PS1-Vin)") (class "Default")
      (node (ref "C5") (pin "2") (pinfunction "2_2") (pintype "passive"))
      (node (ref "C8") (pin "2") (pinfunction "2_2") (pintype "passive"))
      (node (ref "CONN3") (pin "1") (pinfunction "1_1") (pintype "passive"))
      (node (ref "CONN3") (pin "2") (pinfunction "2_2") (pintype "passive"))
      (node (ref "PS1") (pin "1") (pinfunction "Vin_1") (pintype "input"))
    )
    (net (code "55") (name "Net-(R11-WIPER)") (class "Default")
      (node (ref "R11") (pin "2") (pinfunction "WIPER_2") (pintype "passive"))
      (node (ref "U2") (pin "15") (pinfunction "R-EXT_15") (pintype "passive"))
      (node (ref "U3") (pin "6") (pinfunction "PW0_6") (pintype "passive"))
    )
    (net (code "56") (name "Net-(R19-Pad1)") (class "Default")
      (node (ref "R19") (pin "1") (pinfunction "1_1") (pintype "passive"))
      (node (ref "SW1") (pin "8") (pinfunction "8_8") (pintype "passive"))
    )
    (net (code "57") (name "Net-(R20-Pad1)") (class "Default")
      (node (ref "R20") (pin "1") (pinfunction "1_1") (pintype "passive"))
      (node (ref "SW1") (pin "7") (pinfunction "7_7") (pintype "passive"))
    )
    (net (code "58") (name "Net-(R21-Pad1)") (class "Default")
      (node (ref "R21") (pin "1") (pinfunction "1_1") (pintype "passive"))
      (node (ref "SW1") (pin "6") (pinfunction "6_6") (pintype "passive"))
    )
    (net (code "59") (name "Net-(R22-Pad1)") (class "Default")
      (node (ref "R22") (pin "1") (pinfunction "1_1") (pintype "passive"))
      (node (ref "SW1") (pin "5") (pinfunction "5_5") (pintype "passive"))
    )
    (net (code "60") (name "Net-(U2-~{OUT0})") (class "Default")
      (node (ref "R3") (pin "1") (pinfunction "1_1") (pintype "passive"))
      (node (ref "U2") (pin "5") (pinfunction "~{OUT0}_5") (pintype "passive"))
    )
    (net (code "61") (name "Net-(U2-~{OUT1})") (class "Default")
      (node (ref "R4") (pin "1") (pinfunction "1_1") (pintype "passive"))
      (node (ref "U2") (pin "6") (pinfunction "~{OUT1}_6") (pintype "passive"))
    )
    (net (code "62") (name "Net-(U2-~{OUT2})") (class "Default")
      (node (ref "R5") (pin "1") (pinfunction "1_1") (pintype "passive"))
      (node (ref "U2") (pin "7") (pinfunction "~{OUT2}_7") (pintype "passive"))
    )
    (net (code "63") (name "Net-(U2-~{OUT3})") (class "Default")
      (node (ref "R6") (pin "1") (pinfunction "1_1") (pintype "passive"))
      (node (ref "U2") (pin "8") (pinfunction "~{OUT3}_8") (pintype "passive"))
    )
    (net (code "64") (name "Net-(U2-~{OUT4})") (class "Default")
      (node (ref "R7") (pin "1") (pinfunction "1_1") (pintype "passive"))
      (node (ref "U2") (pin "9") (pinfunction "~{OUT4}_9") (pintype "passive"))
    )
    (net (code "65") (name "Net-(U2-~{OUT5})") (class "Default")
      (node (ref "R8") (pin "1") (pinfunction "1_1") (pintype "passive"))
      (node (ref "U2") (pin "10") (pinfunction "~{OUT5}_10") (pintype "passive"))
    )
    (net (code "66") (name "Net-(U2-~{OUT6})") (class "Default")
      (node (ref "R9") (pin "1") (pinfunction "1_1") (pintype "passive"))
      (node (ref "U2") (pin "11") (pinfunction "~{OUT6}_11") (pintype "passive"))
    )
    (net (code "67") (name "Net-(U2-~{OUT7})") (class "Default")
      (node (ref "R10") (pin "1") (pinfunction "1_1") (pintype "passive"))
      (node (ref "U2") (pin "12") (pinfunction "~{OUT7}_12") (pintype "passive"))
    )
    (net (code "68") (name "Net-(U4-VBAT)") (class "Default")
      (node (ref "BATT1") (pin "+") (pinfunction "+_+") (pintype "passive"))
      (node (ref "U4") (pin "3") (pinfunction "VBAT_3") (pintype "passive"))
    )
    (net (code "69") (name "Net-(U4-X1)") (class "Default")
      (node (ref "U4") (pin "1") (pinfunction "X1_1") (pintype "passive"))
      (node (ref "XTAL1") (pin "2") (pinfunction "2_2") (pintype "passive"))
    )
    (net (code "70") (name "Net-(U4-X2)") (class "Default")
      (node (ref "U4") (pin "2") (pinfunction "X2_2") (pintype "passive"))
      (node (ref "XTAL1") (pin "1") (pinfunction "1_1") (pintype "passive"))
    )
    (net (code "71") (name "unconnected-(LED1-ANODE_1-Pad14)") (class "Default")
      (node (ref "LED1") (pin "14") (pinfunction "ANODE_1_14") (pintype "passive"))
    )
    (net (code "72") (name "unconnected-(LED1-ANODE_2-Pad11)") (class "Default")
      (node (ref "LED1") (pin "11") (pinfunction "ANODE_2_11") (pintype "passive"))
    )
    (net (code "73") (name "unconnected-(LED1-ANODE_3-Pad10)") (class "Default")
      (node (ref "LED1") (pin "10") (pinfunction "ANODE_3_10") (pintype "passive"))
    )
    (net (code "74") (name "unconnected-(LED1-ANODE_4-Pad6)") (class "Default")
      (node (ref "LED1") (pin "6") (pinfunction "ANODE_4_6") (pintype "passive"))
    )
    (net (code "75") (name "unconnected-(LED1-ANODE_COLON-Pad7)") (class "Default")
      (node (ref "LED1") (pin "7") (pinfunction "ANODE_COLON_7") (pintype "passive"))
    )
    (net (code "76") (name "unconnected-(LED1-CATHODE_A-Pad13)") (class "Default")
      (node (ref "LED1") (pin "13") (pinfunction "CATHODE_A_13") (pintype "passive"))
    )
    (net (code "77") (name "unconnected-(LED1-CATHODE_B-Pad9)") (class "Default")
      (node (ref "LED1") (pin "9") (pinfunction "CATHODE_B_9") (pintype "passive"))
    )
    (net (code "78") (name "unconnected-(LED1-CATHODE_C-Pad4)") (class "Default")
      (node (ref "LED1") (pin "4") (pinfunction "CATHODE_C_4") (pintype "passive"))
    )
    (net (code "79") (name "unconnected-(LED1-CATHODE_COLON-Pad8)") (class "Default")
      (node (ref "LED1") (pin "8") (pinfunction "CATHODE_COLON_8") (pintype "passive"))
    )
    (net (code "80") (name "unconnected-(LED1-CATHODE_D-Pad2)") (class "Default")
      (node (ref "LED1") (pin "2") (pinfunction "CATHODE_D_2") (pintype "passive"))
    )
    (net (code "81") (name "unconnected-(LED1-CATHODE_DP-Pad3)") (class "Default")
      (node (ref "LED1") (pin "3") (pinfunction "CATHODE_DP_3") (pintype "passive"))
    )
    (net (code "82") (name "unconnected-(LED1-CATHODE_E-Pad1)") (class "Default")
      (node (ref "LED1") (pin "1") (pinfunction "CATHODE_E_1") (pintype "passive"))
    )
    (net (code "83") (name "unconnected-(LED1-CATHODE_F-Pad12)") (class "Default")
      (node (ref "LED1") (pin "12") (pinfunction "CATHODE_F_12") (pintype "passive"))
    )
    (net (code "84") (name "unconnected-(LED1-CATHODE_G-Pad5)") (class "Default")
      (node (ref "LED1") (pin "5") (pinfunction "CATHODE_G_5") (pintype "passive"))
    )
    (net (code "85") (name "unconnected-(LED2-ANODE_1-Pad1)") (class "Default")
      (node (ref "LED2") (pin "1") (pinfunction "ANODE_1_1") (pintype "passive"))
    )
    (net (code "86") (name "unconnected-(LED2-ANODE_2-Pad6)") (class "Default")
      (node (ref "LED2") (pin "6") (pinfunction "ANODE_2_6") (pintype "passive"))
    )
    (net (code "87") (name "unconnected-(LED2-CATHODE_A-Pad10)") (class "Default")
      (node (ref "LED2") (pin "10") (pinfunction "CATHODE_A_10") (pintype "passive"))
    )
    (net (code "88") (name "unconnected-(LED2-CATHODE_B-Pad9)") (class "Default")
      (node (ref "LED2") (pin "9") (pinfunction "CATHODE_B_9") (pintype "passive"))
    )
    (net (code "89") (name "unconnected-(LED2-CATHODE_C-Pad8)") (class "Default")
      (node (ref "LED2") (pin "8") (pinfunction "CATHODE_C_8") (pintype "passive"))
    )
    (net (code "90") (name "unconnected-(LED2-CATHODE_D-Pad5)") (class "Default")
      (node (ref "LED2") (pin "5") (pinfunction "CATHODE_D_5") (pintype "passive"))
    )
    (net (code "91") (name "unconnected-(LED2-CATHODE_DP-Pad7)") (class "Default")
      (node (ref "LED2") (pin "7") (pinfunction "CATHODE_DP_7") (pintype "passive"))
    )
    (net (code "92") (name "unconnected-(LED2-CATHODE_E-Pad4)") (class "Default")
      (node (ref "LED2") (pin "4") (pinfunction "CATHODE_E_4") (pintype "passive"))
    )
    (net (code "93") (name "unconnected-(LED2-CATHODE_F-Pad2)") (class "Default")
      (node (ref "LED2") (pin "2") (pinfunction "CATHODE_F_2") (pintype "passive"))
    )
    (net (code "94") (name "unconnected-(LED2-CATHODE_G-Pad3)") (class "Default")
      (node (ref "LED2") (pin "3") (pinfunction "CATHODE_G_3") (pintype "passive"))
    )
    (net (code "95") (name "unconnected-(LED4-ANODE_1-Pad1)") (class "Default")
      (node (ref "LED4") (pin "1") (pinfunction "ANODE_1_1") (pintype "passive"))
    )
    (net (code "96") (name "unconnected-(LED4-ANODE_2-Pad6)") (class "Default")
      (node (ref "LED4") (pin "6") (pinfunction "ANODE_2_6") (pintype "passive"))
    )
    (net (code "97") (name "unconnected-(LED4-CATHODE_A-Pad10)") (class "Default")
      (node (ref "LED4") (pin "10") (pinfunction "CATHODE_A_10") (pintype "passive"))
    )
    (net (code "98") (name "unconnected-(LED4-CATHODE_B-Pad9)") (class "Default")
      (node (ref "LED4") (pin "9") (pinfunction "CATHODE_B_9") (pintype "passive"))
    )
    (net (code "99") (name "unconnected-(LED4-CATHODE_C-Pad8)") (class "Default")
      (node (ref "LED4") (pin "8") (pinfunction "CATHODE_C_8") (pintype "passive"))
    )
    (net (code "100") (name "unconnected-(LED4-CATHODE_D-Pad5)") (class "Default")
      (node (ref "LED4") (pin "5") (pinfunction "CATHODE_D_5") (pintype "passive"))
    )
    (net (code "101") (name "unconnected-(LED4-CATHODE_DP-Pad7)") (class "Default")
      (node (ref "LED4") (pin "7") (pinfunction "CATHODE_DP_7") (pintype "passive"))
    )
    (net (code "102") (name "unconnected-(LED4-CATHODE_E-Pad4)") (class "Default")
      (node (ref "LED4") (pin "4") (pinfunction "CATHODE_E_4") (pintype "passive"))
    )
    (net (code "103") (name "unconnected-(LED4-CATHODE_F-Pad2)") (class "Default")
      (node (ref "LED4") (pin "2") (pinfunction "CATHODE_F_2") (pintype "passive"))
    )
    (net (code "104") (name "unconnected-(LED4-CATHODE_G-Pad3)") (class "Default")
      (node (ref "LED4") (pin "3") (pinfunction "CATHODE_G_3") (pintype "passive"))
    )
    (net (code "105") (name "unconnected-(R11-CW-Pad3)") (class "Default")
      (node (ref "R11") (pin "3") (pinfunction "CW_3") (pintype "passive"))
    )
    (net (code "106") (name "unconnected-(U1-NC_1-Pad12)") (class "Default")
      (node (ref "U1") (pin "12") (pinfunction "NC_1_12") (pintype "passive"))
    )
    (net (code "107") (name "unconnected-(U1-NC_2-Pad13)") (class "Default")
      (node (ref "U1") (pin "13") (pinfunction "NC_2_13") (pintype "passive"))
    )
    (net (code "108") (name "unconnected-(U1-NC_3-Pad33)") (class "Default")
      (node (ref "U1") (pin "33") (pinfunction "NC_3_33") (pintype "passive"))
    )
    (net (code "109") (name "unconnected-(U1-NC_4-Pad34)") (class "Default")
      (node (ref "U1") (pin "34") (pinfunction "NC_4_34") (pintype "passive"))
    )
    (net (code "110") (name "unconnected-(U1-RE0{slash}~{RD}{slash}AN5-Pad25)") (class "Default")
      (node (ref "U1") (pin "25") (pinfunction "RE0/~{RD}/AN5_25") (pintype "passive"))
    )
    (net (code "111") (name "unconnected-(U1-RE1{slash}~{WR}{slash}AN6-Pad26)") (class "Default")
      (node (ref "U1") (pin "26") (pinfunction "RE1/~{WR}/AN6_26") (pintype "passive"))
    )
    (net (code "112") (name "unconnected-(U1-RE2{slash}~{CS}{slash}AN7-Pad27)") (class "Default")
      (node (ref "U1") (pin "27") (pinfunction "RE2/~{CS}/AN7_27") (pintype "passive"))
    )
    (net (code "113") (name "unconnected-(U2-SDO-Pad14)") (class "Default")
      (node (ref "U2") (pin "14") (pinfunction "SDO_14") (pintype "passive"))
    )
    (net (code "114") (name "unconnected-(U3-PA0-Pad5)") (class "Default")
      (node (ref "U3") (pin "5") (pinfunction "PA0_5") (pintype "passive"))
    )
  )
)
